# H_bridge_PNP_NPN_transistors.net
KiCad netlist of a schematic drawn in EAGLE
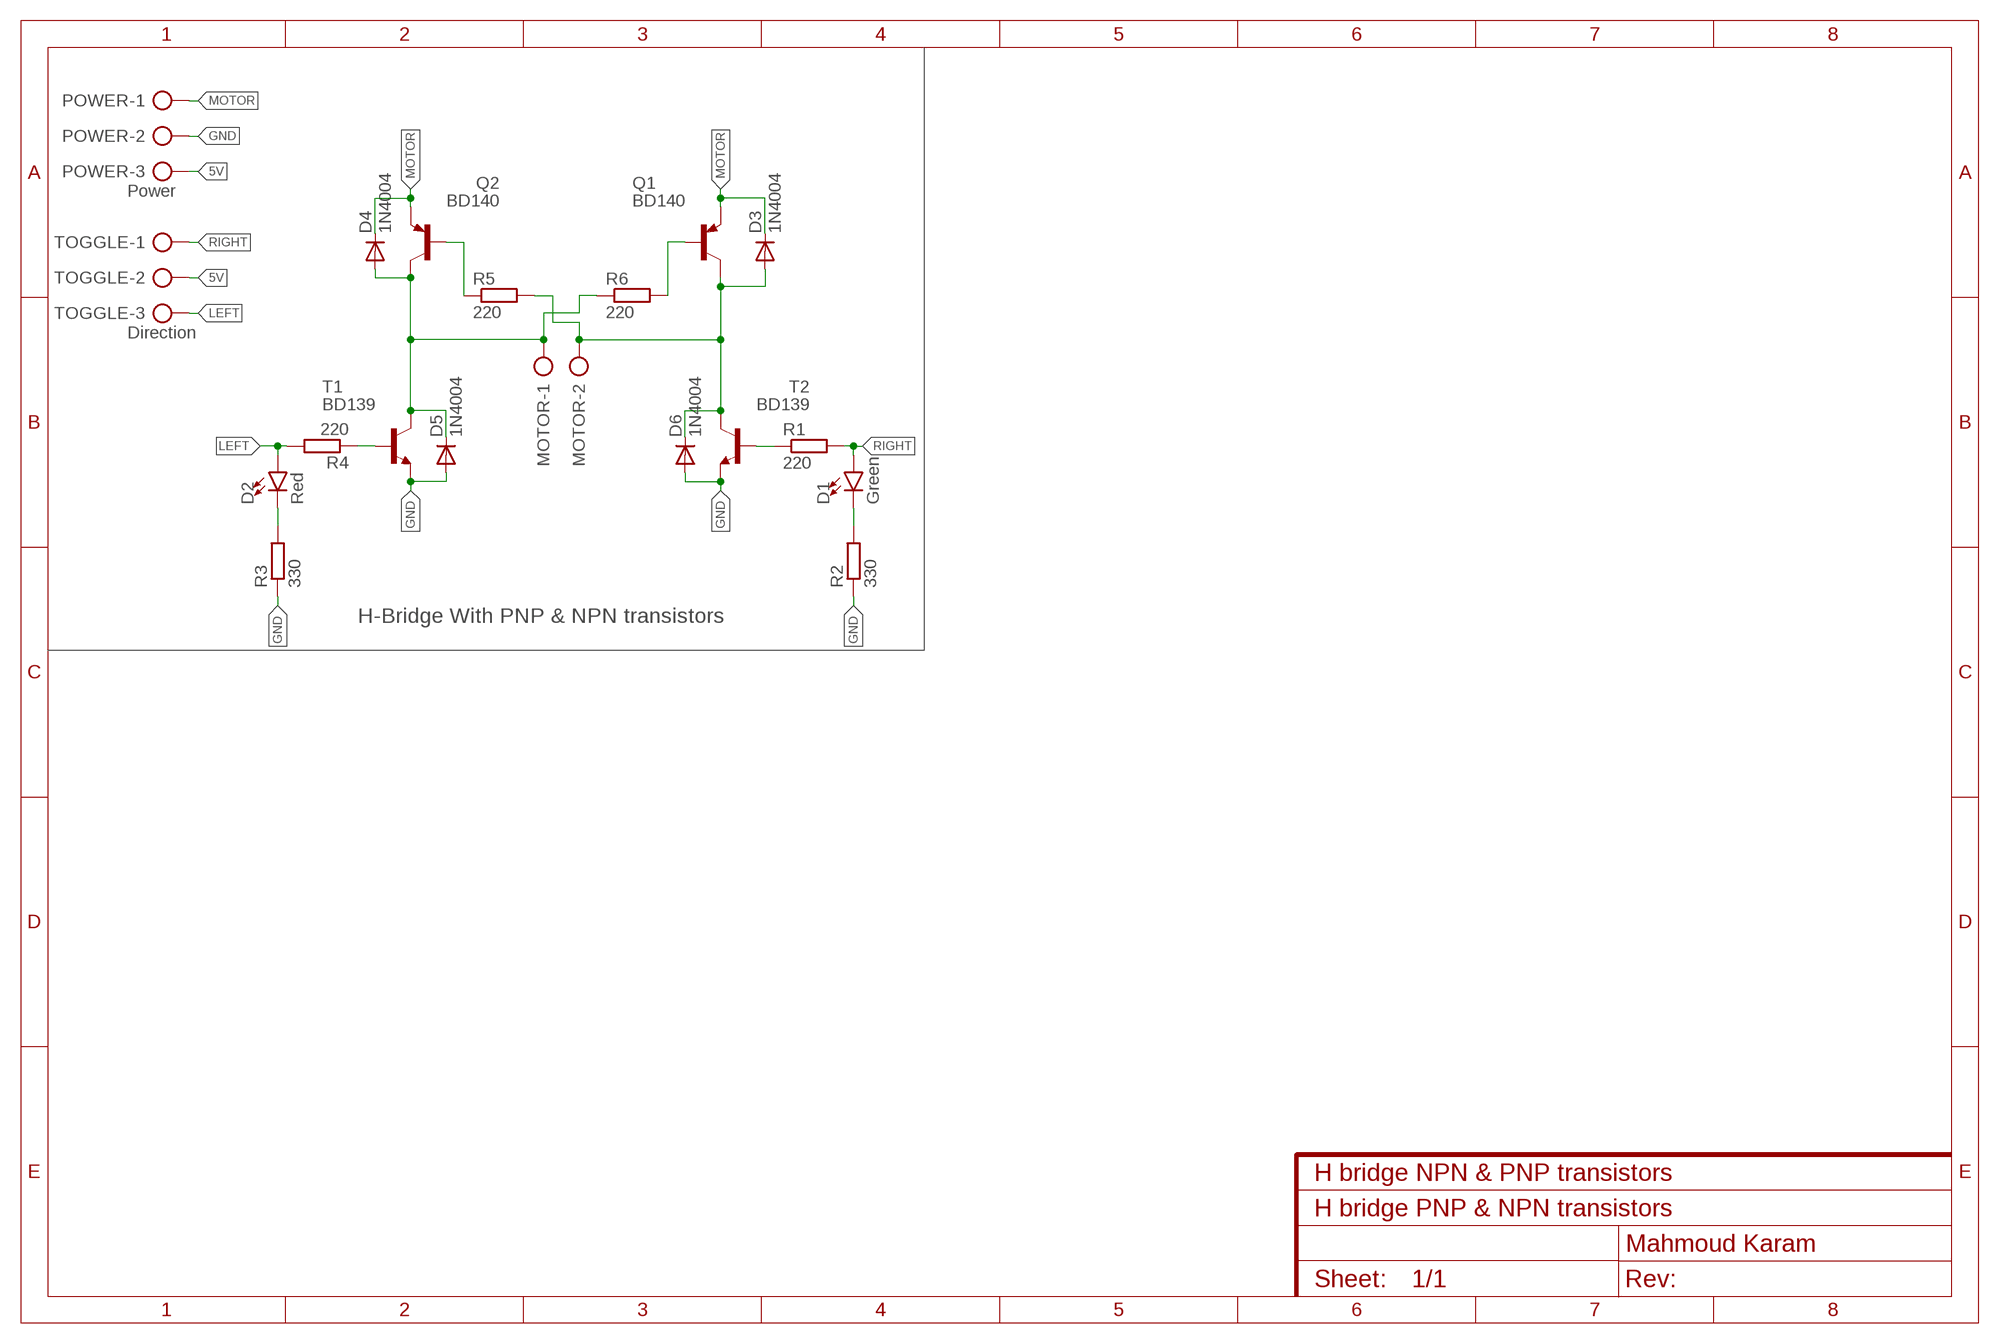
[diagram p0: schematic, sheet 1]

(export (version "E")
  (design (tool "Eeschema 10.0.6"))
  (components
    (comp (ref "D1")
      (value "Green")
      (footprint "eagle-import:LED_5MM")
      (libsource (lib "eagle-import") (part "LED5MM"))
    )
    (comp (ref "D2")
      (value "Red")
      (footprint "eagle-import:LED_5MM")
      (libsource (lib "eagle-import") (part "LED5MM"))
    )
    (comp (ref "D3")
      (value "1N4004")
      (footprint "eagle-import:DO41-10")
      (libsource (lib "eagle-import") (part "1N4004"))
    )
    (comp (ref "D4")
      (value "1N4004")
      (footprint "eagle-import:DO41-10")
      (libsource (lib "eagle-import") (part "1N4004"))
    )
    (comp (ref "D5")
      (value "1N4004")
      (footprint "eagle-import:DO41-10")
      (libsource (lib "eagle-import") (part "1N4004"))
    )
    (comp (ref "D6")
      (value "1N4004")
      (footprint "eagle-import:DO41-10")
      (libsource (lib "eagle-import") (part "1N4004"))
    )
    (comp (ref "MOTOR")
      (value "AK500/2-H")
      (footprint "eagle-import:AK500_2-H")
      (libsource (lib "eagle-import") (part "AK500/2-H"))
    )
    (comp (ref "POWER")
      (value "Power")
      (footprint "eagle-import:AK500_3-H")
      (libsource (lib "eagle-import") (part "AK500/3-H"))
    )
    (comp (ref "Q1")
      (value "BD140")
      (footprint "eagle-import:TO126")
      (libsource (lib "eagle-import") (part "BD140"))
    )
    (comp (ref "Q2")
      (value "BD140")
      (footprint "eagle-import:TO126")
      (libsource (lib "eagle-import") (part "BD140"))
    )
    (comp (ref "R1")
      (value "220")
      (footprint "eagle-import:0207_7")
      (libsource (lib "eagle-import") (part "R-EU_0207/7"))
    )
    (comp (ref "R2")
      (value "330")
      (footprint "eagle-import:0207_7")
      (libsource (lib "eagle-import") (part "R-EU_0207/7"))
    )
    (comp (ref "R3")
      (value "330")
      (footprint "eagle-import:0207_7")
      (libsource (lib "eagle-import") (part "R-EU_0207/7"))
    )
    (comp (ref "R4")
      (value "220")
      (footprint "eagle-import:0207_7")
      (libsource (lib "eagle-import") (part "R-EU_0207/7"))
    )
    (comp (ref "R5")
      (value "220")
      (footprint "eagle-import:0207_7")
      (libsource (lib "eagle-import") (part "R-EU_0207/7"))
    )
    (comp (ref "R6")
      (value "220")
      (footprint "eagle-import:0207_7")
      (libsource (lib "eagle-import") (part "R-EU_0207/7"))
    )
    (comp (ref "T1")
      (value "BD139")
      (footprint "eagle-import:TO126")
      (libsource (lib "eagle-import") (part "BD139"))
    )
    (comp (ref "T2")
      (value "BD139")
      (footprint "eagle-import:TO126")
      (libsource (lib "eagle-import") (part "BD139"))
    )
    (comp (ref "TOGGLE")
      (value "Direction")
      (footprint "eagle-import:AK500_3-H")
      (libsource (lib "eagle-import") (part "AK500/3-H"))
    )
  )
  (nets
    (net (code "1") (name "5V") (class "Default")
      (node (ref "POWER") (pin "3") (pinfunction "KL_3") (pintype "passive"))
      (node (ref "TOGGLE") (pin "2") (pinfunction "KL_2") (pintype "passive"))
    )
    (net (code "2") (name "GND") (class "Default")
      (node (ref "D5") (pin "A") (pinfunction "A_A") (pintype "passive"))
      (node (ref "D6") (pin "A") (pinfunction "A_A") (pintype "passive"))
      (node (ref "POWER") (pin "2") (pinfunction "KL_2") (pintype "passive"))
      (node (ref "R2") (pin "1") (pinfunction "1_1") (pintype "passive"))
      (node (ref "R3") (pin "1") (pinfunction "1_1") (pintype "passive"))
      (node (ref "T1") (pin "1") (pinfunction "E_1") (pintype "passive"))
      (node (ref "T2") (pin "1") (pinfunction "E_1") (pintype "passive"))
    )
    (net (code "3") (name "LEFT") (class "Default")
      (node (ref "D2") (pin "A") (pinfunction "A_A") (pintype "passive"))
      (node (ref "R4") (pin "2") (pinfunction "2_2") (pintype "passive"))
      (node (ref "TOGGLE") (pin "3") (pinfunction "KL_3") (pintype "passive"))
    )
    (net (code "4") (name "MOTOR") (class "Default")
      (node (ref "D3") (pin "C") (pinfunction "C_C") (pintype "passive"))
      (node (ref "D4") (pin "C") (pinfunction "C_C") (pintype "passive"))
      (node (ref "POWER") (pin "1") (pinfunction "KL_1") (pintype "passive"))
      (node (ref "Q1") (pin "1") (pinfunction "E_1") (pintype "passive"))
      (node (ref "Q2") (pin "1") (pinfunction "E_1") (pintype "passive"))
    )
    (net (code "5") (name "Net-(D1-C)") (class "Default")
      (node (ref "D1") (pin "K") (pinfunction "C_K") (pintype "passive"))
      (node (ref "R2") (pin "2") (pinfunction "2_2") (pintype "passive"))
    )
    (net (code "6") (name "Net-(D2-C)") (class "Default")
      (node (ref "D2") (pin "K") (pinfunction "C_K") (pintype "passive"))
      (node (ref "R3") (pin "2") (pinfunction "2_2") (pintype "passive"))
    )
    (net (code "7") (name "Net-(MOTORA-KL)") (class "Default")
      (node (ref "D4") (pin "A") (pinfunction "A_A") (pintype "passive"))
      (node (ref "D5") (pin "C") (pinfunction "C_C") (pintype "passive"))
      (node (ref "MOTOR") (pin "1") (pinfunction "KL_1") (pintype "passive"))
      (node (ref "Q2") (pin "2") (pinfunction "C_2") (pintype "passive"))
      (node (ref "R6") (pin "1") (pinfunction "1_1") (pintype "passive"))
      (node (ref "T1") (pin "2") (pinfunction "C_2") (pintype "passive"))
    )
    (net (code "8") (name "Net-(MOTORB-KL)") (class "Default")
      (node (ref "D3") (pin "A") (pinfunction "A_A") (pintype "passive"))
      (node (ref "D6") (pin "C") (pinfunction "C_C") (pintype "passive"))
      (node (ref "MOTOR") (pin "2") (pinfunction "KL_2") (pintype "passive"))
      (node (ref "Q1") (pin "2") (pinfunction "C_2") (pintype "passive"))
      (node (ref "R5") (pin "2") (pinfunction "2_2") (pintype "passive"))
      (node (ref "T2") (pin "2") (pinfunction "C_2") (pintype "passive"))
    )
    (net (code "9") (name "Net-(Q1-B)") (class "Default")
      (node (ref "Q1") (pin "3") (pinfunction "B_3") (pintype "passive"))
      (node (ref "R6") (pin "2") (pinfunction "2_2") (pintype "passive"))
    )
    (net (code "10") (name "Net-(Q2-B)") (class "Default")
      (node (ref "Q2") (pin "3") (pinfunction "B_3") (pintype "passive"))
      (node (ref "R5") (pin "1") (pinfunction "1_1") (pintype "passive"))
    )
    (net (code "11") (name "Net-(T1-B)") (class "Default")
      (node (ref "R4") (pin "1") (pinfunction "1_1") (pintype "passive"))
      (node (ref "T1") (pin "3") (pinfunction "B_3") (pintype "passive"))
    )
    (net (code "12") (name "Net-(T2-B)") (class "Default")
      (node (ref "R1") (pin "1") (pinfunction "1_1") (pintype "passive"))
      (node (ref "T2") (pin "3") (pinfunction "B_3") (pintype "passive"))
    )
    (net (code "13") (name "RIGHT") (class "Default")
      (node (ref "D1") (pin "A") (pinfunction "A_A") (pintype "passive"))
      (node (ref "R1") (pin "2") (pinfunction "2_2") (pintype "passive"))
      (node (ref "TOGGLE") (pin "1") (pinfunction "KL_1") (pintype "passive"))
    )
  )
)
